# BMS_MCU.net
KiCad netlist of a schematic drawn in Altium Designer
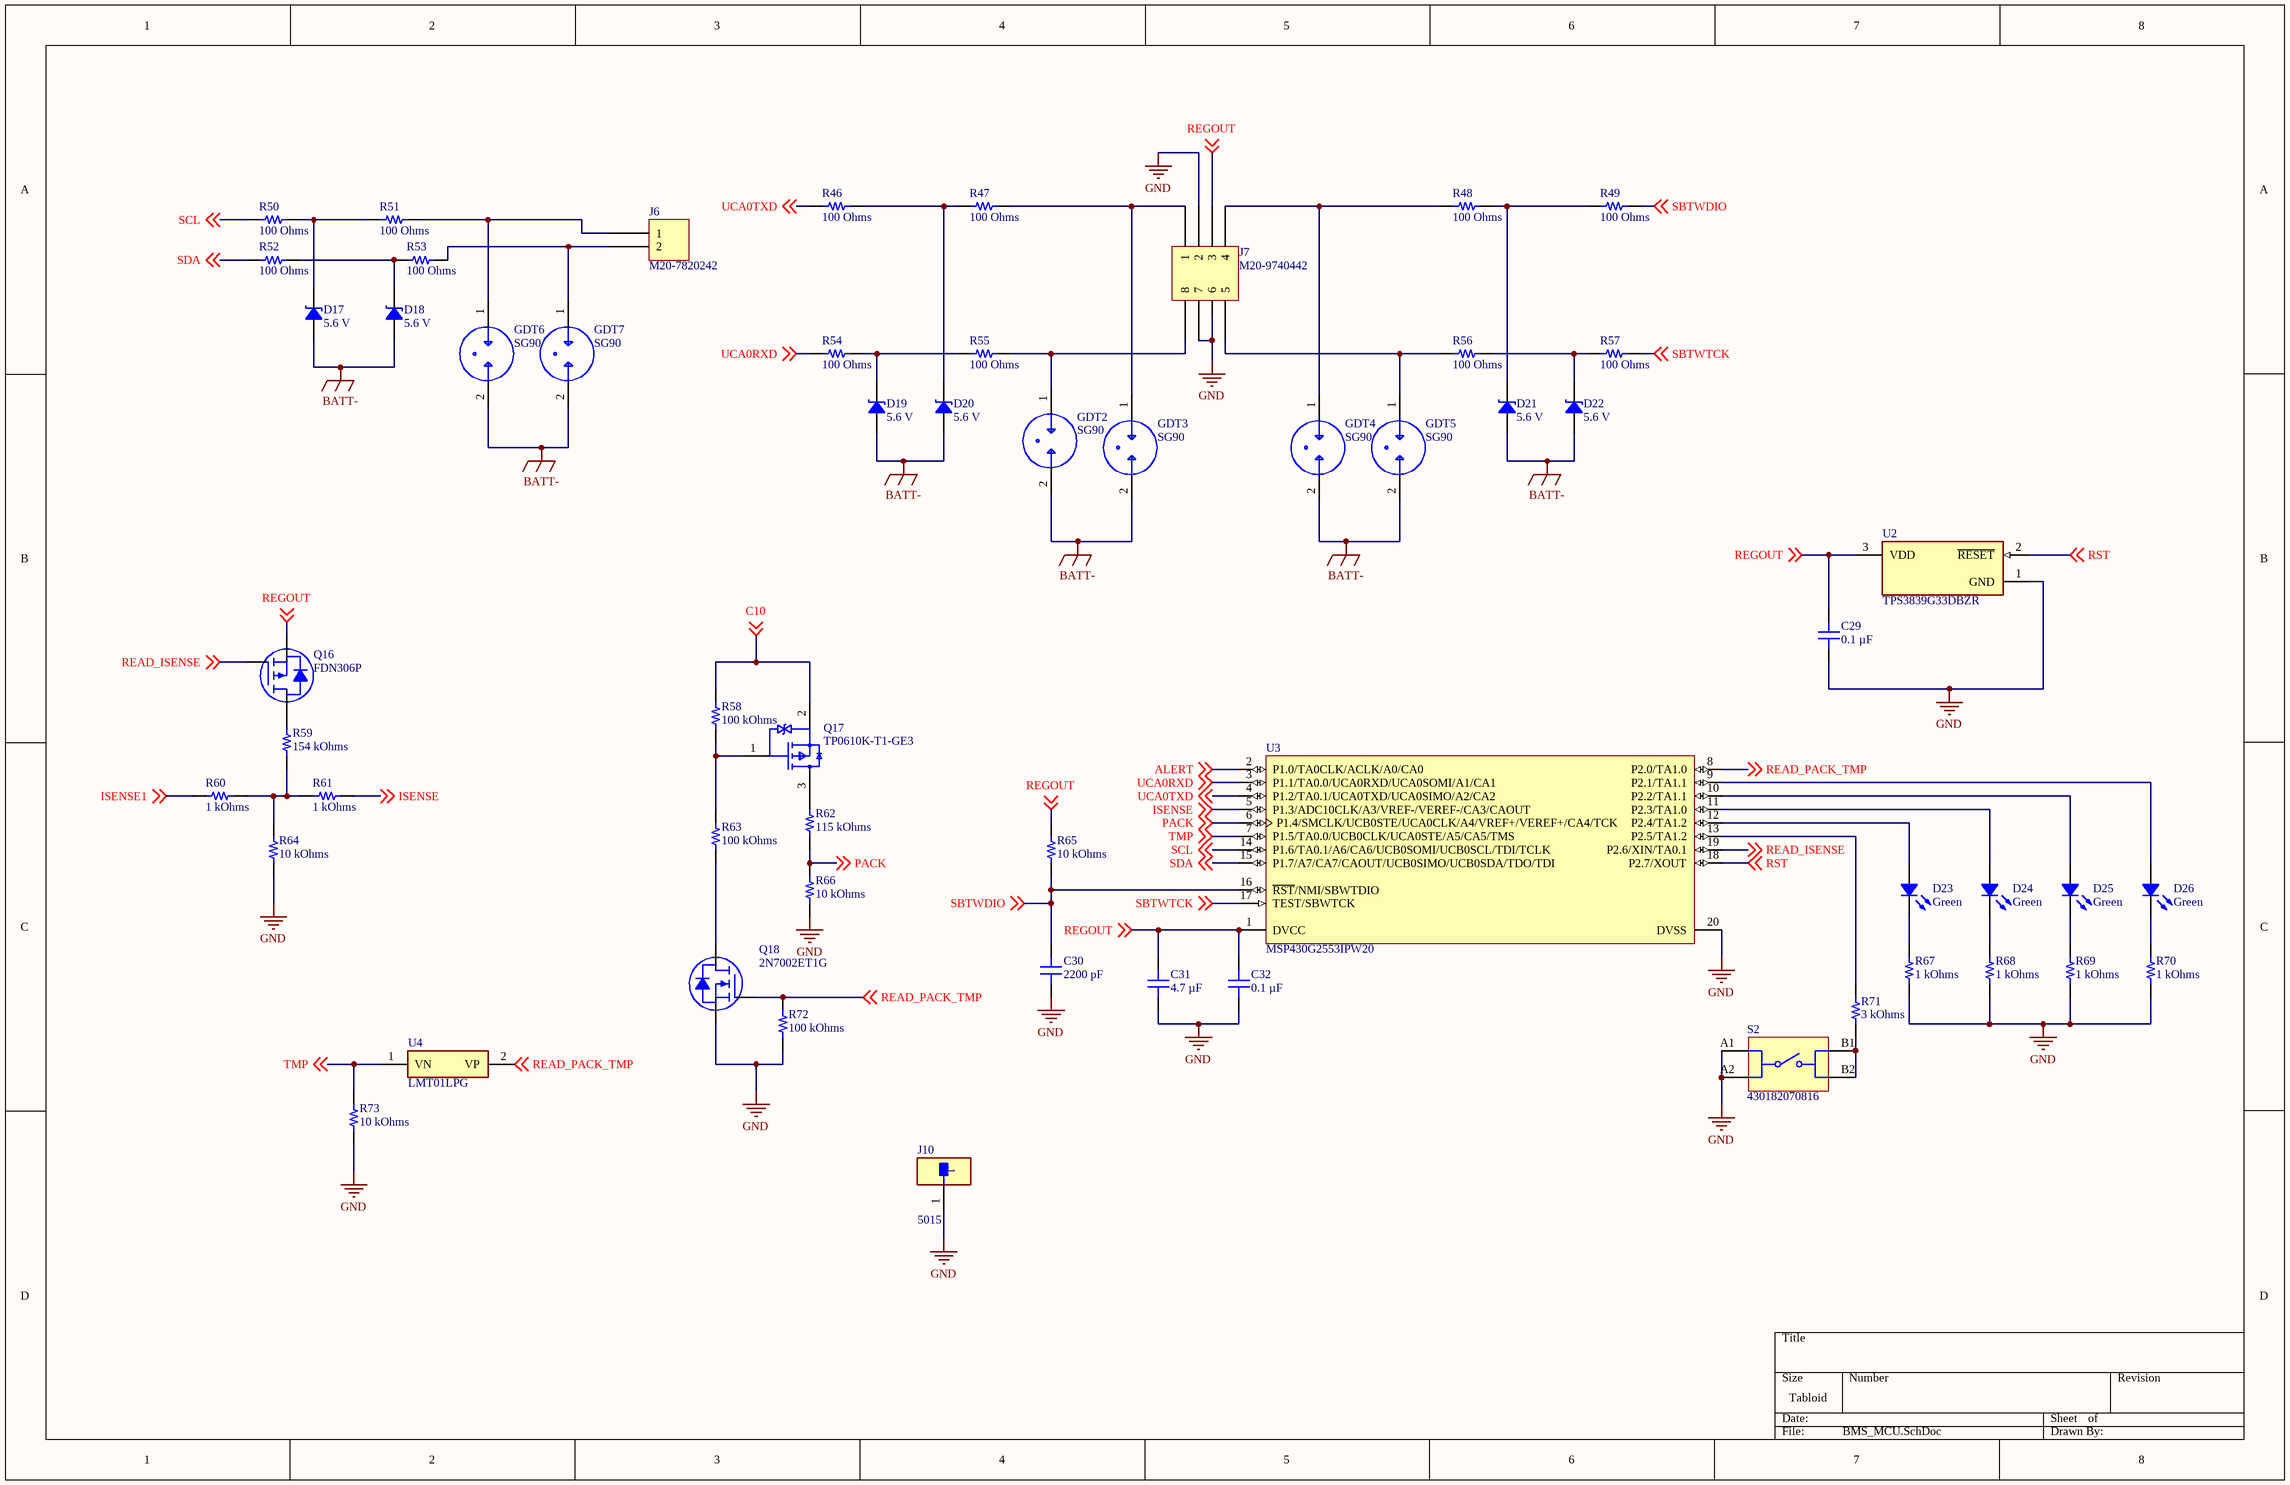
[diagram p0: BMS_MCU.SchDoc]

(export (version "E")
  (design (tool "Eeschema 10.0.6"))
  (components
    (comp (ref "C29")
      (value "0.1 µF")
      (footprint "CAP 0603_1608")
      (description "CAP CER 0.1UF 16V X7R 0603")
      (fields
        (field (name "PART NUMBER") "885012206046")
        (field (name "CAPACITANCE") "0.1 µF")
        (field (name "MANUFACTURER") "Würth Elektronik")
      )
      (libsource (lib "Celestial Altium Library - altium_library") (part "Capacitor"))
    )
    (comp (ref "C30")
      (value "2200 pF")
      (footprint "CAP 0603_1608")
      (description "CAP CER 2200PF 16V X7R 0603")
      (fields
        (field (name "PART NUMBER") "885012206036")
        (field (name "CAPACITANCE") "2200 pF")
        (field (name "MANUFACTURER") "Würth Elektronik")
      )
      (libsource (lib "Celestial Altium Library - altium_library") (part "Capacitor"))
    )
    (comp (ref "C31")
      (value "4.7 µF")
      (footprint "CAP 0805_2012")
      (description "CAP CER 4.7UF 10V X7R 0805")
      (fields
        (field (name "PART NUMBER") "885012207025")
        (field (name "CAPACITANCE") "4.7 µF")
        (field (name "MANUFACTURER") "Würth Elektronik")
      )
      (libsource (lib "Celestial Altium Library - altium_library") (part "Capacitor"))
    )
    (comp (ref "C32")
      (value "0.1 µF")
      (footprint "CAP 0603_1608")
      (description "CAP CER 0.1UF 16V X7R 0603")
      (fields
        (field (name "PART NUMBER") "885012206046")
        (field (name "CAPACITANCE") "0.1 µF")
        (field (name "MANUFACTURER") "Würth Elektronik")
      )
      (libsource (lib "Celestial Altium Library - altium_library") (part "Capacitor"))
    )
    (comp (ref "D17")
      (value "MMSZ5232BS-7-F")
      (footprint "SOD323")
      (description "DIODE ZENER 5.6V 200MW SOD323")
      (fields
        (field (name "MANUFACTURER") "Diodes Incorporated")
        (field (name "TOLERANCE") "±5%")
        (field (name "VOLTAGE - ZENER (NOM) (VZ)") "5.6 V")
      )
      (libsource (lib "Celestial Altium Library - altium_library") (part "Diode Zener"))
    )
    (comp (ref "D18")
      (value "MMSZ5232BS-7-F")
      (footprint "SOD323")
      (description "DIODE ZENER 5.6V 200MW SOD323")
      (fields
        (field (name "MANUFACTURER") "Diodes Incorporated")
        (field (name "TOLERANCE") "±5%")
        (field (name "VOLTAGE - ZENER (NOM) (VZ)") "5.6 V")
      )
      (libsource (lib "Celestial Altium Library - altium_library") (part "Diode Zener"))
    )
    (comp (ref "D19")
      (value "MMSZ5232BS-7-F")
      (footprint "SOD323")
      (description "DIODE ZENER 5.6V 200MW SOD323")
      (fields
        (field (name "MANUFACTURER") "Diodes Incorporated")
        (field (name "TOLERANCE") "±5%")
        (field (name "VOLTAGE - ZENER (NOM) (VZ)") "5.6 V")
      )
      (libsource (lib "Celestial Altium Library - altium_library") (part "Diode Zener"))
    )
    (comp (ref "D20")
      (value "MMSZ5232BS-7-F")
      (footprint "SOD323")
      (description "DIODE ZENER 5.6V 200MW SOD323")
      (fields
        (field (name "MANUFACTURER") "Diodes Incorporated")
        (field (name "TOLERANCE") "±5%")
        (field (name "VOLTAGE - ZENER (NOM) (VZ)") "5.6 V")
      )
      (libsource (lib "Celestial Altium Library - altium_library") (part "Diode Zener"))
    )
    (comp (ref "D21")
      (value "MMSZ5232BS-7-F")
      (footprint "SOD323")
      (description "DIODE ZENER 5.6V 200MW SOD323")
      (fields
        (field (name "MANUFACTURER") "Diodes Incorporated")
        (field (name "TOLERANCE") "±5%")
        (field (name "VOLTAGE - ZENER (NOM) (VZ)") "5.6 V")
      )
      (libsource (lib "Celestial Altium Library - altium_library") (part "Diode Zener"))
    )
    (comp (ref "D22")
      (value "MMSZ5232BS-7-F")
      (footprint "SOD323")
      (description "DIODE ZENER 5.6V 200MW SOD323")
      (fields
        (field (name "MANUFACTURER") "Diodes Incorporated")
        (field (name "TOLERANCE") "±5%")
        (field (name "VOLTAGE - ZENER (NOM) (VZ)") "5.6 V")
      )
      (libsource (lib "Celestial Altium Library - altium_library") (part "Diode Zener"))
    )
    (comp (ref "D23")
      (value "Green")
      (footprint "LED 0603_1608 GREEN")
      (description "LED GREEN CLEAR 0603 SMD")
      (fields (field (name "PART NUMBER") "150060GS75000") (field (name "MANUFACTURER") "Würth Elektronik"))
      (libsource (lib "Celestial Altium Library - altium_library") (part "LED"))
    )
    (comp (ref "D24")
      (value "Green")
      (footprint "LED 0603_1608 GREEN")
      (description "LED GREEN CLEAR 0603 SMD")
      (fields (field (name "PART NUMBER") "150060GS75000") (field (name "MANUFACTURER") "Würth Elektronik"))
      (libsource (lib "Celestial Altium Library - altium_library") (part "LED"))
    )
    (comp (ref "D25")
      (value "Green")
      (footprint "LED 0603_1608 GREEN")
      (description "LED GREEN CLEAR 0603 SMD")
      (fields (field (name "PART NUMBER") "150060GS75000") (field (name "MANUFACTURER") "Würth Elektronik"))
      (libsource (lib "Celestial Altium Library - altium_library") (part "LED"))
    )
    (comp (ref "D26")
      (value "Green")
      (footprint "LED 0603_1608 GREEN")
      (description "LED GREEN CLEAR 0603 SMD")
      (fields (field (name "PART NUMBER") "150060GS75000") (field (name "MANUFACTURER") "Würth Elektronik"))
      (libsource (lib "Celestial Altium Library - altium_library") (part "LED"))
    )
    (comp (ref "GDT2")
      (value "SG90")
      (footprint "FP-SG-MFG")
      (description "GDT 90V 2KA 2 POLE SURFACE MOUNT")
      (libsource (lib "BMS_MCU") (part "SG90"))
    )
    (comp (ref "GDT3")
      (value "SG90")
      (footprint "FP-SG-MFG")
      (description "GDT 90V 2KA 2 POLE SURFACE MOUNT")
      (libsource (lib "BMS_MCU") (part "SG90"))
    )
    (comp (ref "GDT4")
      (value "SG90")
      (footprint "FP-SG-MFG")
      (description "GDT 90V 2KA 2 POLE SURFACE MOUNT")
      (libsource (lib "BMS_MCU") (part "SG90"))
    )
    (comp (ref "GDT5")
      (value "SG90")
      (footprint "FP-SG-MFG")
      (description "GDT 90V 2KA 2 POLE SURFACE MOUNT")
      (libsource (lib "BMS_MCU") (part "SG90"))
    )
    (comp (ref "GDT6")
      (value "SG90")
      (footprint "FP-SG-MFG")
      (description "GDT 90V 2KA 2 POLE SURFACE MOUNT")
      (libsource (lib "BMS_MCU") (part "SG90"))
    )
    (comp (ref "GDT7")
      (value "SG90")
      (footprint "FP-SG-MFG")
      (description "GDT 90V 2KA 2 POLE SURFACE MOUNT")
      (libsource (lib "BMS_MCU") (part "SG90"))
    )
    (comp (ref "J6")
      (value "M20-7820242")
      (footprint "HARWIN M20-7820245")
      (description "CONN RCPT 2POS 0.1 GOLD PCB")
      (fields (field (name "MANUFACTURER") "Harwin Inc."))
      (libsource (lib "Celestial Altium Library - altium_library") (part "2 Pin"))
    )
    (comp (ref "J7")
      (value "M20-9740442")
      (footprint "HARWIN M20-9740445")
      (description "CONN HEADER R/A 8POS 2.54MM")
      (fields (field (name "MANUFACTURER") "Harwin Inc."))
      (libsource (lib "Celestial Altium Library - altium_library") (part "2X4 PIN DU"))
    )
    (comp (ref "J10")
      (value "5015")
      (footprint "FP-5015-MFG")
      (description "PC TEST POINT MINIATURE")
      (fields
        (field (name "MANUFACTURER") "keystone")
        (field (name "OCTOPART") "https://octopart.com/5015-keystone-3822")
      )
      (libsource (lib "BMS_MCU") (part "Test Point"))
    )
    (comp (ref "Q16")
      (value "FDN306P")
      (footprint "ON SEMI SOT-23-3")
      (description "MOSFET P-CH 12V 2.6A SSOT3")
      (fields (field (name "MANUFACTURER") "ON Semiconductor"))
      (libsource (lib "Celestial Altium Library - altium_library") (part "ON SEMI MOSFET P-CH SOT-23-3"))
    )
    (comp (ref "Q17")
      (value "TP0610K-T1-GE3")
      (footprint "FP-S-03946-IPC_C")
      (description "MOSFET P-CH 60V 185MA SOT23-3")
      (libsource (lib "BMS_FETs") (part "TP0610K-T1-GE3"))
    )
    (comp (ref "Q18")
      (value "2N7002ET1G")
      (footprint "ON SEMI SOT-23-3")
      (description "MOSFET N-CH 60V 260MA SOT-23")
      (fields (field (name "MANUFACTURER") "ON Semiconductor"))
      (libsource (lib "Celestial Altium Library - altium_library") (part "ON SEMI MOSFET N-CH SOT-23-3"))
    )
    (comp (ref "R46")
      (value "100 Ohms")
      (footprint "RES 0805_2012")
      (description "RES SMD 100 OHM 1% 1/8W 0805")
      (fields (field (name "PART NUMBER") "CRCW0805100RFKEA") (field (name "MANUFACTURER") "Vishay Dale"))
      (libsource (lib "Celestial Altium Library - altium_library") (part "Resistor"))
    )
    (comp (ref "R47")
      (value "100 Ohms")
      (footprint "RES 0805_2012")
      (description "RES SMD 100 OHM 1% 1/8W 0805")
      (fields (field (name "PART NUMBER") "CRCW0805100RFKEA") (field (name "MANUFACTURER") "Vishay Dale"))
      (libsource (lib "Celestial Altium Library - altium_library") (part "Resistor"))
    )
    (comp (ref "R48")
      (value "100 Ohms")
      (footprint "RES 0805_2012")
      (description "RES SMD 100 OHM 1% 1/8W 0805")
      (fields (field (name "PART NUMBER") "CRCW0805100RFKEA") (field (name "MANUFACTURER") "Vishay Dale"))
      (libsource (lib "Celestial Altium Library - altium_library") (part "Resistor"))
    )
    (comp (ref "R49")
      (value "100 Ohms")
      (footprint "RES 0805_2012")
      (description "RES SMD 100 OHM 1% 1/8W 0805")
      (fields (field (name "PART NUMBER") "CRCW0805100RFKEA") (field (name "MANUFACTURER") "Vishay Dale"))
      (libsource (lib "Celestial Altium Library - altium_library") (part "Resistor"))
    )
    (comp (ref "R50")
      (value "100 Ohms")
      (footprint "RES 0805_2012")
      (description "RES SMD 100 OHM 1% 1/8W 0805")
      (fields (field (name "PART NUMBER") "CRCW0805100RFKEA") (field (name "MANUFACTURER") "Vishay Dale"))
      (libsource (lib "Celestial Altium Library - altium_library") (part "Resistor"))
    )
    (comp (ref "R51")
      (value "100 Ohms")
      (footprint "RES 0805_2012")
      (description "RES SMD 100 OHM 1% 1/8W 0805")
      (fields (field (name "PART NUMBER") "CRCW0805100RFKEA") (field (name "MANUFACTURER") "Vishay Dale"))
      (libsource (lib "Celestial Altium Library - altium_library") (part "Resistor"))
    )
    (comp (ref "R52")
      (value "100 Ohms")
      (footprint "RES 0805_2012")
      (description "RES SMD 100 OHM 1% 1/8W 0805")
      (fields (field (name "PART NUMBER") "CRCW0805100RFKEA") (field (name "MANUFACTURER") "Vishay Dale"))
      (libsource (lib "Celestial Altium Library - altium_library") (part "Resistor"))
    )
    (comp (ref "R53")
      (value "100 Ohms")
      (footprint "RES 0805_2012")
      (description "RES SMD 100 OHM 1% 1/8W 0805")
      (fields (field (name "PART NUMBER") "CRCW0805100RFKEA") (field (name "MANUFACTURER") "Vishay Dale"))
      (libsource (lib "Celestial Altium Library - altium_library") (part "Resistor"))
    )
    (comp (ref "R54")
      (value "100 Ohms")
      (footprint "RES 0805_2012")
      (description "RES SMD 100 OHM 1% 1/8W 0805")
      (fields (field (name "PART NUMBER") "CRCW0805100RFKEA") (field (name "MANUFACTURER") "Vishay Dale"))
      (libsource (lib "Celestial Altium Library - altium_library") (part "Resistor"))
    )
    (comp (ref "R55")
      (value "100 Ohms")
      (footprint "RES 0805_2012")
      (description "RES SMD 100 OHM 1% 1/8W 0805")
      (fields (field (name "PART NUMBER") "CRCW0805100RFKEA") (field (name "MANUFACTURER") "Vishay Dale"))
      (libsource (lib "Celestial Altium Library - altium_library") (part "Resistor"))
    )
    (comp (ref "R56")
      (value "100 Ohms")
      (footprint "RES 0805_2012")
      (description "RES SMD 100 OHM 1% 1/8W 0805")
      (fields (field (name "PART NUMBER") "CRCW0805100RFKEA") (field (name "MANUFACTURER") "Vishay Dale"))
      (libsource (lib "Celestial Altium Library - altium_library") (part "Resistor"))
    )
    (comp (ref "R57")
      (value "100 Ohms")
      (footprint "RES 0805_2012")
      (description "RES SMD 100 OHM 1% 1/8W 0805")
      (fields (field (name "PART NUMBER") "CRCW0805100RFKEA") (field (name "MANUFACTURER") "Vishay Dale"))
      (libsource (lib "Celestial Altium Library - altium_library") (part "Resistor"))
    )
    (comp (ref "R58")
      (value "100 kOhms")
      (footprint "RES 0603_1608")
      (description "RES SMD 100K OHM 5% 1/10W 0603")
      (fields (field (name "PART NUMBER") "CRCW0603100KJNEA") (field (name "MANUFACTURER") "Vishay Dale"))
      (libsource (lib "Celestial Altium Library - altium_library") (part "Resistor"))
    )
    (comp (ref "R59")
      (value "154 kOhms")
      (footprint "RES 0603_1608")
      (description "RES SMD 154K OHM 1% 1/10W 0603")
      (fields (field (name "PART NUMBER") "CRCW0603154KFKEA") (field (name "MANUFACTURER") "Vishay Dale"))
      (libsource (lib "Celestial Altium Library - altium_library") (part "Resistor"))
    )
    (comp (ref "R60")
      (value "1 kOhms")
      (footprint "RES 0603_1608")
      (description "RES SMD 1K OHM 5% 1/10W 0603")
      (fields (field (name "PART NUMBER") "CRCW06031K00JNEA") (field (name "MANUFACTURER") "Vishay Dale"))
      (libsource (lib "Celestial Altium Library - altium_library") (part "Resistor"))
    )
    (comp (ref "R61")
      (value "1 kOhms")
      (footprint "RES 0603_1608")
      (description "RES SMD 1K OHM 5% 1/10W 0603")
      (fields (field (name "PART NUMBER") "CRCW06031K00JNEA") (field (name "MANUFACTURER") "Vishay Dale"))
      (libsource (lib "Celestial Altium Library - altium_library") (part "Resistor"))
    )
    (comp (ref "R62")
      (value "115 kOhms")
      (footprint "RES 0603_1608")
      (description "RES SMD 115K OHM 1% 1/10W 0603")
      (fields (field (name "PART NUMBER") "CRCW0603115KFKEA") (field (name "MANUFACTURER") "Vishay Dale"))
      (libsource (lib "Celestial Altium Library - altium_library") (part "Resistor"))
    )
    (comp (ref "R63")
      (value "100 kOhms")
      (footprint "RES 0603_1608")
      (description "RES SMD 100K OHM 5% 1/10W 0603")
      (fields (field (name "PART NUMBER") "CRCW0603100KJNEA") (field (name "MANUFACTURER") "Vishay Dale"))
      (libsource (lib "Celestial Altium Library - altium_library") (part "Resistor"))
    )
    (comp (ref "R64")
      (value "10 kOhms")
      (footprint "RES 0603_1608")
      (description "RES SMD 10K OHM 1% 1/10W 0603")
      (fields (field (name "PART NUMBER") "CRCW060310K0FKEA") (field (name "MANUFACTURER") "Vishay Dale"))
      (libsource (lib "Celestial Altium Library - altium_library") (part "Resistor"))
    )
    (comp (ref "R65")
      (value "10 kOhms")
      (footprint "RES 0603_1608")
      (description "RES SMD 10K OHM 1% 1/10W 0603")
      (fields (field (name "PART NUMBER") "CRCW060310K0FKEA") (field (name "MANUFACTURER") "Vishay Dale"))
      (libsource (lib "Celestial Altium Library - altium_library") (part "Resistor"))
    )
    (comp (ref "R66")
      (value "10 kOhms")
      (footprint "RES 0603_1608")
      (description "RES SMD 10K OHM 1% 1/10W 0603")
      (fields (field (name "PART NUMBER") "CRCW060310K0FKEA") (field (name "MANUFACTURER") "Vishay Dale"))
      (libsource (lib "Celestial Altium Library - altium_library") (part "Resistor"))
    )
    (comp (ref "R67")
      (value "1 kOhms")
      (footprint "RES 0603_1608")
      (description "RES SMD 1K OHM 5% 1/10W 0603")
      (fields (field (name "PART NUMBER") "CRCW06031K00JNEA") (field (name "MANUFACTURER") "Vishay Dale"))
      (libsource (lib "Celestial Altium Library - altium_library") (part "Resistor"))
    )
    (comp (ref "R68")
      (value "1 kOhms")
      (footprint "RES 0603_1608")
      (description "RES SMD 1K OHM 5% 1/10W 0603")
      (fields (field (name "PART NUMBER") "CRCW06031K00JNEA") (field (name "MANUFACTURER") "Vishay Dale"))
      (libsource (lib "Celestial Altium Library - altium_library") (part "Resistor"))
    )
    (comp (ref "R69")
      (value "1 kOhms")
      (footprint "RES 0603_1608")
      (description "RES SMD 1K OHM 5% 1/10W 0603")
      (fields (field (name "PART NUMBER") "CRCW06031K00JNEA") (field (name "MANUFACTURER") "Vishay Dale"))
      (libsource (lib "Celestial Altium Library - altium_library") (part "Resistor"))
    )
    (comp (ref "R70")
      (value "1 kOhms")
      (footprint "RES 0603_1608")
      (description "RES SMD 1K OHM 5% 1/10W 0603")
      (fields (field (name "PART NUMBER") "CRCW06031K00JNEA") (field (name "MANUFACTURER") "Vishay Dale"))
      (libsource (lib "Celestial Altium Library - altium_library") (part "Resistor"))
    )
    (comp (ref "R71")
      (value "3 kOhms")
      (footprint "RES 0603_1608")
      (description "RES SMD 3K OHM 5% 1/10W 0603")
      (fields (field (name "PART NUMBER") "CRCW06033K00JNEA") (field (name "MANUFACTURER") "Vishay Dale"))
      (libsource (lib "Celestial Altium Library - altium_library") (part "Resistor"))
    )
    (comp (ref "R72")
      (value "100 kOhms")
      (footprint "RES 0603_1608")
      (description "RES SMD 100K OHM 5% 1/10W 0603")
      (fields (field (name "PART NUMBER") "CRCW0603100KJNEA") (field (name "MANUFACTURER") "Vishay Dale"))
      (libsource (lib "Celestial Altium Library - altium_library") (part "Resistor"))
    )
    (comp (ref "R73")
      (value "10 kOhms")
      (footprint "RES 0603_1608")
      (description "RES SMD 10K OHM 1% 1/10W 0603")
      (fields (field (name "PART NUMBER") "CRCW060310K0FKEA") (field (name "MANUFACTURER") "Vishay Dale"))
      (libsource (lib "Celestial Altium Library - altium_library") (part "Resistor"))
    )
    (comp (ref "S2")
      (value "430182070816")
      (footprint "430182070816")
      (description "Switch Tactile Spst-no 0.05A 12V")
      (libsource (lib "BMS_AFE") (part "430182070816"))
    )
    (comp (ref "U2")
      (value "TPS3839G33DBZR")
      (footprint "FP-DBZ0003A-MFG")
      (description "IC SUPERVISOR 1 CHANNEL SOT23-3")
      (libsource (lib "BMS_MCU") (part "TPS3839G33DBZR"))
    )
    (comp (ref "U3")
      (value "MSP430G2553IPW20")
      (footprint "PW0020A_L")
      (fields (field (name "MANUFACTURER") "Texas Instruments"))
      (libsource (lib "BMS_MCU") (part "MSP430G2553IPW20"))
    )
    (comp (ref "U4")
      (value "LMT01LPG")
      (footprint "FP-LPG0002A-MFG")
      (description "SENSOR DIGITAL -50C-150C TO92-2")
      (fields
        (field (name "OCTOPART") "https://octopart.com/lmt01lpg-texas+instruments-60770464")
        (field (name "MANUFACTURER") "Texas Instruments")
      )
      (libsource (lib "BMS_MCU") (part "LMT01LPG"))
    )
  )
  (nets
    (net (code "1") (name "ALERT") (class "Default")
      (node (ref "U3") (pin "2") (pinfunction "P1.0/TA0CLK/ACLK/A0/CA0_2") (pintype "bidirectional"))
    )
    (net (code "2") (name "BATT-") (class "Default")
      (node (ref "D17") (pin "1") (pinfunction "1_1") (pintype "passive"))
      (node (ref "D18") (pin "1") (pinfunction "1_1") (pintype "passive"))
      (node (ref "D19") (pin "1") (pinfunction "1_1") (pintype "passive"))
      (node (ref "D20") (pin "1") (pinfunction "1_1") (pintype "passive"))
      (node (ref "D21") (pin "1") (pinfunction "1_1") (pintype "passive"))
      (node (ref "D22") (pin "1") (pinfunction "1_1") (pintype "passive"))
      (node (ref "GDT2") (pin "2") (pinfunction "2_2") (pintype "passive"))
      (node (ref "GDT3") (pin "2") (pinfunction "2_2") (pintype "passive"))
      (node (ref "GDT4") (pin "2") (pinfunction "2_2") (pintype "passive"))
      (node (ref "GDT5") (pin "2") (pinfunction "2_2") (pintype "passive"))
      (node (ref "GDT6") (pin "2") (pinfunction "2_2") (pintype "passive"))
      (node (ref "GDT7") (pin "2") (pinfunction "2_2") (pintype "passive"))
    )
    (net (code "3") (name "C10") (class "Default")
      (node (ref "Q17") (pin "2") (pinfunction "S_2") (pintype "passive"))
      (node (ref "R58") (pin "2") (pinfunction "2_2") (pintype "passive"))
    )
    (net (code "4") (name "GND") (class "Default")
      (node (ref "C29") (pin "1") (pinfunction "1_1") (pintype "passive"))
      (node (ref "C30") (pin "1") (pinfunction "1_1") (pintype "passive"))
      (node (ref "C31") (pin "1") (pinfunction "1_1") (pintype "passive"))
      (node (ref "C32") (pin "1") (pinfunction "1_1") (pintype "passive"))
      (node (ref "J10") (pin "1") (pinfunction "1_1") (pintype "passive"))
      (node (ref "J7") (pin "2") (pinfunction "2_2") (pintype "passive"))
      (node (ref "J7") (pin "6") (pinfunction "6_6") (pintype "passive"))
      (node (ref "J7") (pin "7") (pinfunction "7_7") (pintype "passive"))
      (node (ref "Q18") (pin "2") (pinfunction "S_2") (pintype "passive"))
      (node (ref "R64") (pin "1") (pinfunction "1_1") (pintype "passive"))
      (node (ref "R66") (pin "1") (pinfunction "1_1") (pintype "passive"))
      (node (ref "R67") (pin "1") (pinfunction "1_1") (pintype "passive"))
      (node (ref "R68") (pin "1") (pinfunction "1_1") (pintype "passive"))
      (node (ref "R69") (pin "1") (pinfunction "1_1") (pintype "passive"))
      (node (ref "R70") (pin "1") (pinfunction "1_1") (pintype "passive"))
      (node (ref "R72") (pin "1") (pinfunction "1_1") (pintype "passive"))
      (node (ref "R73") (pin "1") (pinfunction "1_1") (pintype "passive"))
      (node (ref "S2") (pin "A1") (pinfunction "A1_A1") (pintype "passive"))
      (node (ref "S2") (pin "A2") (pinfunction "A2_A2") (pintype "passive"))
      (node (ref "U2") (pin "1") (pinfunction "GND_1") (pintype "power_in"))
      (node (ref "U3") (pin "20") (pinfunction "DVSS_20") (pintype "power_in"))
    )
    (net (code "5") (name "ISENSE") (class "Default")
      (node (ref "R61") (pin "2") (pinfunction "2_2") (pintype "passive"))
      (node (ref "U3") (pin "5") (pinfunction "P1.3/ADC10CLK/A3/VREF-/VEREF-/CA3/CAOUT_5") (pintype "bidirectional"))
    )
    (net (code "6") (name "ISENSE1") (class "Default")
      (node (ref "R60") (pin "1") (pinfunction "1_1") (pintype "passive"))
    )
    (net (code "7") (name "Net-(D17-Pad2)") (class "Default")
      (node (ref "D17") (pin "2") (pinfunction "2_2") (pintype "passive"))
      (node (ref "R50") (pin "1") (pinfunction "1_1") (pintype "passive"))
      (node (ref "R51") (pin "2") (pinfunction "2_2") (pintype "passive"))
    )
    (net (code "8") (name "Net-(D18-Pad2)") (class "Default")
      (node (ref "D18") (pin "2") (pinfunction "2_2") (pintype "passive"))
      (node (ref "R52") (pin "1") (pinfunction "1_1") (pintype "passive"))
      (node (ref "R53") (pin "2") (pinfunction "2_2") (pintype "passive"))
    )
    (net (code "9") (name "Net-(D19-Pad2)") (class "Default")
      (node (ref "D19") (pin "2") (pinfunction "2_2") (pintype "passive"))
      (node (ref "R54") (pin "1") (pinfunction "1_1") (pintype "passive"))
      (node (ref "R55") (pin "2") (pinfunction "2_2") (pintype "passive"))
    )
    (net (code "10") (name "Net-(D20-Pad2)") (class "Default")
      (node (ref "D20") (pin "2") (pinfunction "2_2") (pintype "passive"))
      (node (ref "R46") (pin "1") (pinfunction "1_1") (pintype "passive"))
      (node (ref "R47") (pin "2") (pinfunction "2_2") (pintype "passive"))
    )
    (net (code "11") (name "Net-(D21-Pad2)") (class "Default")
      (node (ref "D21") (pin "2") (pinfunction "2_2") (pintype "passive"))
      (node (ref "R48") (pin "1") (pinfunction "1_1") (pintype "passive"))
      (node (ref "R49") (pin "2") (pinfunction "2_2") (pintype "passive"))
    )
    (net (code "12") (name "Net-(D22-Pad2)") (class "Default")
      (node (ref "D22") (pin "2") (pinfunction "2_2") (pintype "passive"))
      (node (ref "R56") (pin "1") (pinfunction "1_1") (pintype "passive"))
      (node (ref "R57") (pin "2") (pinfunction "2_2") (pintype "passive"))
    )
    (net (code "13") (name "Net-(D23-Pad2)") (class "Default")
      (node (ref "D23") (pin "2") (pinfunction "2_2") (pintype "passive"))
      (node (ref "R67") (pin "2") (pinfunction "2_2") (pintype "passive"))
    )
    (net (code "14") (name "Net-(D24-Pad2)") (class "Default")
      (node (ref "D24") (pin "2") (pinfunction "2_2") (pintype "passive"))
      (node (ref "R68") (pin "2") (pinfunction "2_2") (pintype "passive"))
    )
    (net (code "15") (name "Net-(D25-Pad2)") (class "Default")
      (node (ref "D25") (pin "2") (pinfunction "2_2") (pintype "passive"))
      (node (ref "R69") (pin "2") (pinfunction "2_2") (pintype "passive"))
    )
    (net (code "16") (name "Net-(D26-Pad2)") (class "Default")
      (node (ref "D26") (pin "2") (pinfunction "2_2") (pintype "passive"))
      (node (ref "R70") (pin "2") (pinfunction "2_2") (pintype "passive"))
    )
    (net (code "17") (name "Net-(GDT2-Pad1)") (class "Default")
      (node (ref "GDT2") (pin "1") (pinfunction "1_1") (pintype "passive"))
      (node (ref "J7") (pin "8") (pinfunction "8_8") (pintype "passive"))
      (node (ref "R55") (pin "1") (pinfunction "1_1") (pintype "passive"))
    )
    (net (code "18") (name "Net-(GDT3-Pad1)") (class "Default")
      (node (ref "GDT3") (pin "1") (pinfunction "1_1") (pintype "passive"))
      (node (ref "J7") (pin "1") (pinfunction "1_1") (pintype "passive"))
      (node (ref "R47") (pin "1") (pinfunction "1_1") (pintype "passive"))
    )
    (net (code "19") (name "Net-(GDT4-Pad1)") (class "Default")
      (node (ref "GDT4") (pin "1") (pinfunction "1_1") (pintype "passive"))
      (node (ref "J7") (pin "4") (pinfunction "4_4") (pintype "passive"))
      (node (ref "R48") (pin "2") (pinfunction "2_2") (pintype "passive"))
    )
    (net (code "20") (name "Net-(GDT5-Pad1)") (class "Default")
      (node (ref "GDT5") (pin "1") (pinfunction "1_1") (pintype "passive"))
      (node (ref "J7") (pin "5") (pinfunction "5_5") (pintype "passive"))
      (node (ref "R56") (pin "2") (pinfunction "2_2") (pintype "passive"))
    )
    (net (code "21") (name "Net-(GDT6-Pad1)") (class "Default")
      (node (ref "GDT6") (pin "1") (pinfunction "1_1") (pintype "passive"))
      (node (ref "J6") (pin "1") (pinfunction "1_1") (pintype "passive"))
      (node (ref "R51") (pin "1") (pinfunction "1_1") (pintype "passive"))
    )
    (net (code "22") (name "Net-(GDT7-Pad1)") (class "Default")
      (node (ref "GDT7") (pin "1") (pinfunction "1_1") (pintype "passive"))
      (node (ref "J6") (pin "2") (pinfunction "2_2") (pintype "passive"))
      (node (ref "R53") (pin "1") (pinfunction "1_1") (pintype "passive"))
    )
    (net (code "23") (name "Net-(Q16-D)") (class "Default")
      (node (ref "Q16") (pin "3") (pinfunction "D_3") (pintype "passive"))
      (node (ref "R59") (pin "2") (pinfunction "2_2") (pintype "passive"))
    )
    (net (code "24") (name "Net-(Q17-D)") (class "Default")
      (node (ref "Q17") (pin "3") (pinfunction "D_3") (pintype "passive"))
      (node (ref "R62") (pin "2") (pinfunction "2_2") (pintype "passive"))
    )
    (net (code "25") (name "Net-(Q17-G)") (class "Default")
      (node (ref "Q17") (pin "1") (pinfunction "G_1") (pintype "passive"))
      (node (ref "R58") (pin "1") (pinfunction "1_1") (pintype "passive"))
      (node (ref "R63") (pin "2") (pinfunction "2_2") (pintype "passive"))
    )
    (net (code "26") (name "Net-(Q18-D)") (class "Default")
      (node (ref "Q18") (pin "3") (pinfunction "D_3") (pintype "passive"))
      (node (ref "R63") (pin "1") (pinfunction "1_1") (pintype "passive"))
    )
    (net (code "27") (name "Net-(R59-Pad1)") (class "Default")
      (node (ref "R59") (pin "1") (pinfunction "1_1") (pintype "passive"))
      (node (ref "R60") (pin "2") (pinfunction "2_2") (pintype "passive"))
      (node (ref "R61") (pin "1") (pinfunction "1_1") (pintype "passive"))
      (node (ref "R64") (pin "2") (pinfunction "2_2") (pintype "passive"))
    )
    (net (code "28") (name "Net-(R71-Pad1)") (class "Default")
      (node (ref "R71") (pin "1") (pinfunction "1_1") (pintype "passive"))
      (node (ref "S2") (pin "B1") (pinfunction "B1_B1") (pintype "passive"))
      (node (ref "S2") (pin "B2") (pinfunction "B2_B2") (pintype "passive"))
    )
    (net (code "29") (name "Net-(U3-P2.1{slash}TA1.1)") (class "Default")
      (node (ref "D26") (pin "1") (pinfunction "1_1") (pintype "passive"))
      (node (ref "U3") (pin "9") (pinfunction "P2.1/TA1.1_9") (pintype "bidirectional"))
    )
    (net (code "30") (name "Net-(U3-P2.2{slash}TA1.1)") (class "Default")
      (node (ref "D25") (pin "1") (pinfunction "1_1") (pintype "passive"))
      (node (ref "U3") (pin "10") (pinfunction "P2.2/TA1.1_10") (pintype "bidirectional"))
    )
    (net (code "31") (name "Net-(U3-P2.3{slash}TA1.0)") (class "Default")
      (node (ref "D24") (pin "1") (pinfunction "1_1") (pintype "passive"))
      (node (ref "U3") (pin "11") (pinfunction "P2.3/TA1.0_11") (pintype "bidirectional"))
    )
    (net (code "32") (name "Net-(U3-P2.4{slash}TA1.2)") (class "Default")
      (node (ref "D23") (pin "1") (pinfunction "1_1") (pintype "passive"))
      (node (ref "U3") (pin "12") (pinfunction "P2.4/TA1.2_12") (pintype "bidirectional"))
    )
    (net (code "33") (name "Net-(U3-P2.5{slash}TA1.2)") (class "Default")
      (node (ref "R71") (pin "2") (pinfunction "2_2") (pintype "passive"))
      (node (ref "U3") (pin "13") (pinfunction "P2.5/TA1.2_13") (pintype "bidirectional"))
    )
    (net (code "34") (name "PACK") (class "Default")
      (node (ref "R62") (pin "1") (pinfunction "1_1") (pintype "passive"))
      (node (ref "R66") (pin "2") (pinfunction "2_2") (pintype "passive"))
      (node (ref "U3") (pin "6") (pinfunction "P1.4/SMCLK/UCB0STE/UCA0CLK/A4/VREF+/VEREF+/CA4/TCK_6") (pintype "bidirectional"))
    )
    (net (code "35") (name "READ_ISENSE") (class "Default")
      (node (ref "Q16") (pin "1") (pinfunction "G_1") (pintype "passive"))
      (node (ref "U3") (pin "19") (pinfunction "P2.6/XIN/TA0.1_19") (pintype "bidirectional"))
    )
    (net (code "36") (name "READ_PACK_TMP") (class "Default")
      (node (ref "Q18") (pin "1") (pinfunction "G_1") (pintype "passive"))
      (node (ref "R72") (pin "2") (pinfunction "2_2") (pintype "passive"))
      (node (ref "U3") (pin "8") (pinfunction "P2.0/TA1.0_8") (pintype "bidirectional"))
      (node (ref "U4") (pin "2") (pinfunction "VP_2") (pintype "passive"))
    )
    (net (code "37") (name "REGOUT") (class "Default")
      (node (ref "C29") (pin "2") (pinfunction "2_2") (pintype "passive"))
      (node (ref "C31") (pin "2") (pinfunction "2_2") (pintype "passive"))
      (node (ref "C32") (pin "2") (pinfunction "2_2") (pintype "passive"))
      (node (ref "J7") (pin "3") (pinfunction "3_3") (pintype "passive"))
      (node (ref "Q16") (pin "2") (pinfunction "S_2") (pintype "passive"))
      (node (ref "R65") (pin "2") (pinfunction "2_2") (pintype "passive"))
      (node (ref "U2") (pin "3") (pinfunction "VDD_3") (pintype "power_in"))
      (node (ref "U3") (pin "1") (pinfunction "DVCC_1") (pintype "power_in"))
    )
    (net (code "38") (name "RST") (class "Default")
      (node (ref "U2") (pin "2") (pinfunction "~{RESET}_2") (pintype "input"))
      (node (ref "U3") (pin "18") (pinfunction "P2.7/XOUT_18") (pintype "bidirectional"))
    )
    (net (code "39") (name "SBTWDIO") (class "Default")
      (node (ref "C30") (pin "2") (pinfunction "2_2") (pintype "passive"))
      (node (ref "R49") (pin "1") (pinfunction "1_1") (pintype "passive"))
      (node (ref "R65") (pin "1") (pinfunction "1_1") (pintype "passive"))
      (node (ref "U3") (pin "16") (pinfunction "~{RST}/NMI/SBWTDIO_16") (pintype "bidirectional"))
    )
    (net (code "40") (name "SBTWTCK") (class "Default")
      (node (ref "R57") (pin "1") (pinfunction "1_1") (pintype "passive"))
      (node (ref "U3") (pin "17") (pinfunction "TEST/SBWTCK_17") (pintype "input"))
    )
    (net (code "41") (name "SCL") (class "Default")
      (node (ref "R50") (pin "2") (pinfunction "2_2") (pintype "passive"))
      (node (ref "U3") (pin "14") (pinfunction "P1.6/TA0.1/A6/CA6/UCB0SOMI/UCB0SCL/TDI/TCLK_14") (pintype "bidirectional"))
    )
    (net (code "42") (name "SDA") (class "Default")
      (node (ref "R52") (pin "2") (pinfunction "2_2") (pintype "passive"))
      (node (ref "U3") (pin "15") (pinfunction "P1.7/A7/CA7/CAOUT/UCB0SIMO/UCB0SDA/TDO/TDI_15") (pintype "bidirectional"))
    )
    (net (code "43") (name "TMP") (class "Default")
      (node (ref "R73") (pin "2") (pinfunction "2_2") (pintype "passive"))
      (node (ref "U3") (pin "7") (pinfunction "P1.5/TA0.0/UCB0CLK/UCA0STE/A5/CA5/TMS_7") (pintype "bidirectional"))
      (node (ref "U4") (pin "1") (pinfunction "VN_1") (pintype "passive"))
    )
    (net (code "44") (name "UCA0RXD") (class "Default")
      (node (ref "R54") (pin "2") (pinfunction "2_2") (pintype "passive"))
      (node (ref "U3") (pin "3") (pinfunction "P1.1/TA0.0/UCA0RXD/UCA0SOMI/A1/CA1_3") (pintype "bidirectional"))
    )
    (net (code "45") (name "UCA0TXD") (class "Default")
      (node (ref "R46") (pin "2") (pinfunction "2_2") (pintype "passive"))
      (node (ref "U3") (pin "4") (pinfunction "P1.2/TA0.1/UCA0TXD/UCA0SIMO/A2/CA2_4") (pintype "bidirectional"))
    )
  )
)
